# Power.net
KiCad netlist of a schematic drawn in Altium Designer
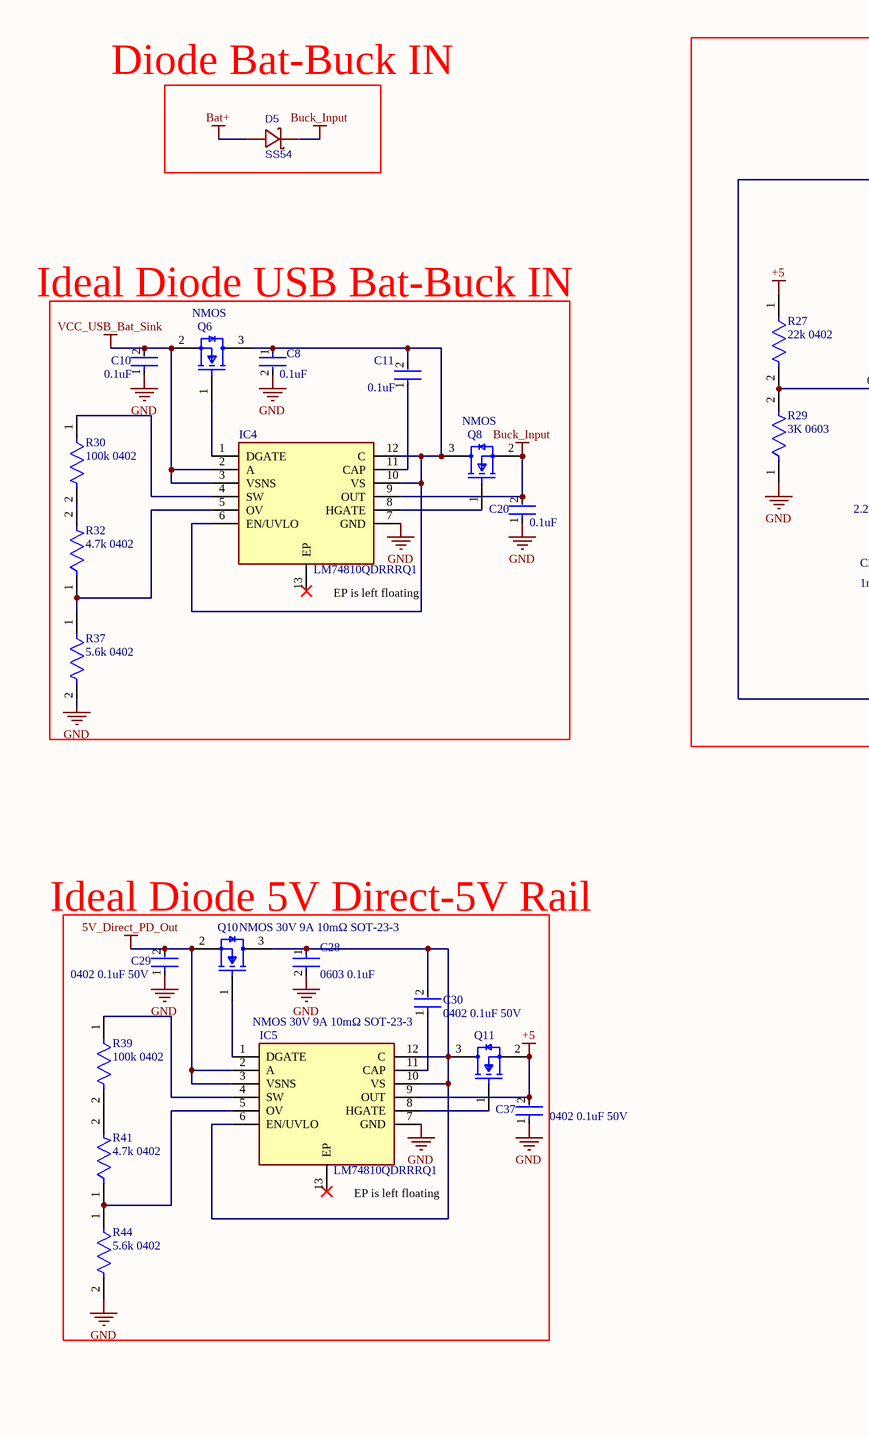
[diagram p0: Power.SchDoc, left]
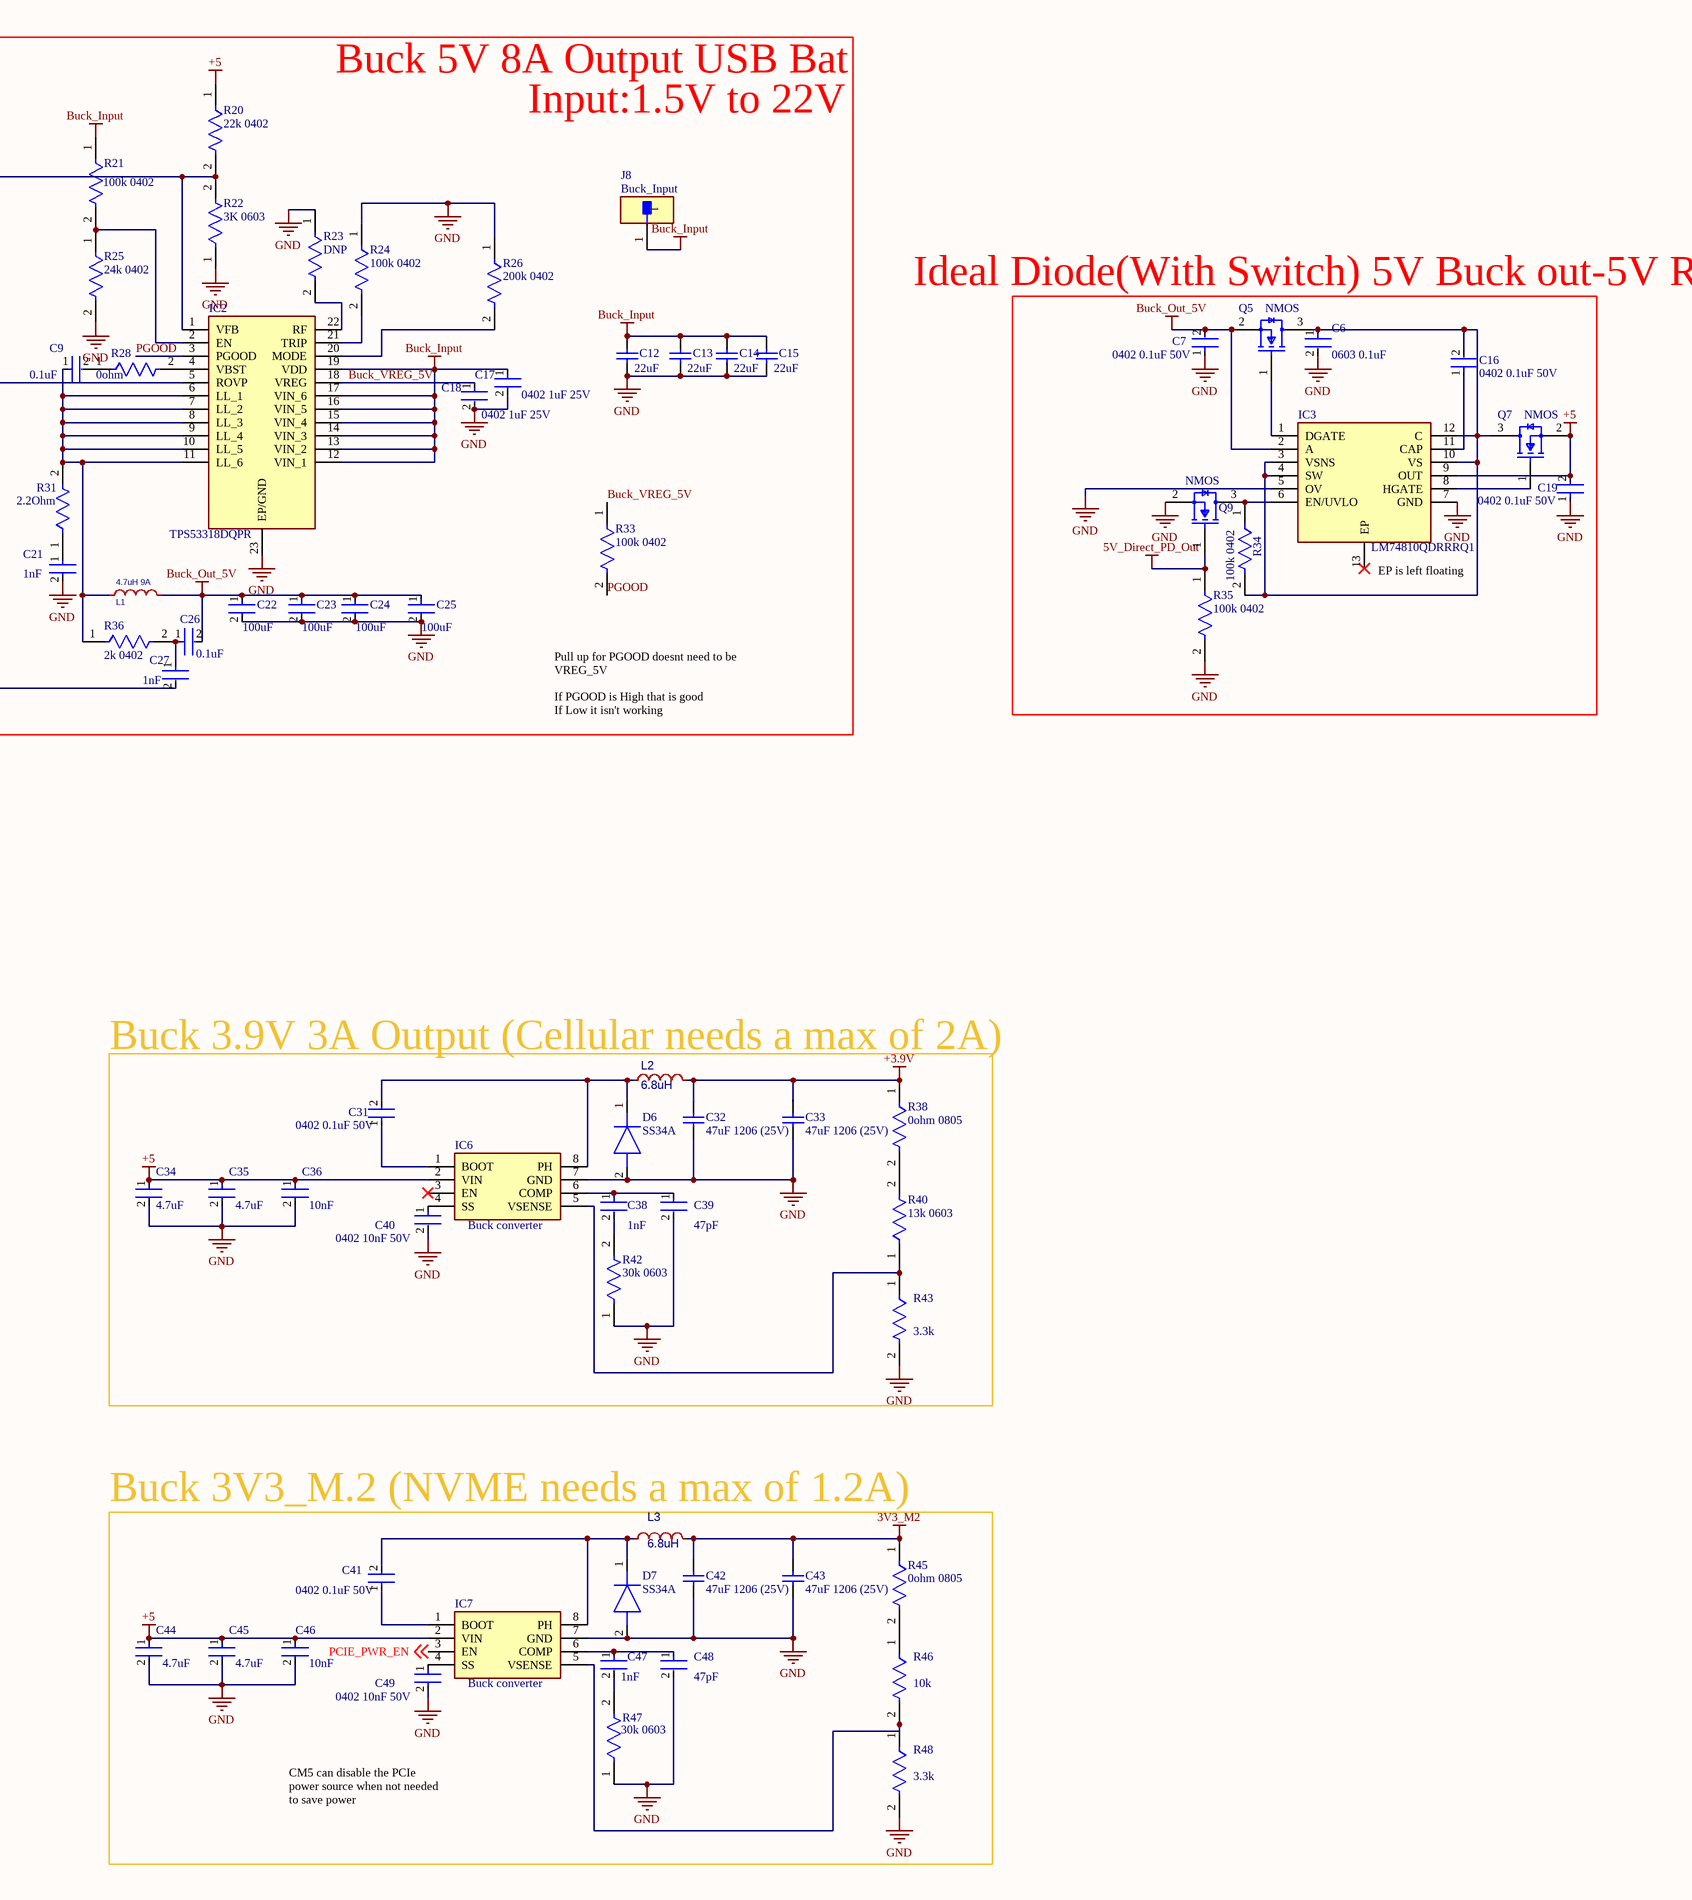
[diagram p1: Power.SchDoc, right]

(export (version "E")
  (design (tool "Eeschema 10.0.6"))
  (components
    (comp (ref "C6")
      (value "0603 0.1uF")
      (footprint "FP-CC0603-DC-MFG")
      (description "C14663")
      (fields (field (name "TOLERANCE") "10%"))
      (libsource (lib "Altium Content Vault") (part "b4654b650e69147ec39a6b967a45e02"))
    )
    (comp (ref "C7")
      (value "0402 0.1uF 50V")
      (footprint "FP-C0402-BB-MFG")
      (description "C307331")
      (fields
        (field (name "TOLERANCE") "0.2")
        (field (name "OCTOPART") "https://octopart.com/c0402c104m3pac7867-kemet-84304880")
      )
      (libsource (lib "Altium Content Vault") (part "b4654b650e69147ec39a6b967a45e02"))
    )
    (comp (ref "C8")
      (value "0.1uF")
      (footprint "FP-CC0603-DC-MFG")
      (description "C14663")
      (fields (field (name "TOLERANCE") "10%"))
      (libsource (lib "Altium Content Vault") (part "b4654b650e69147ec39a6b967a45e02"))
    )
    (comp (ref "C9")
      (value "0.1uF")
      (footprint "FP-C0402-BB-MFG")
      (description "C307331")
      (fields
        (field (name "TOLERANCE") "0.2")
        (field (name "OCTOPART") "https://octopart.com/c0402c104m3pac7867-kemet-84304880")
      )
      (libsource (lib "Altium Content Vault") (part "b4654b650e69147ec39a6b967a45e02"))
    )
    (comp (ref "C10")
      (value "0.1uF")
      (footprint "FP-C0402-BB-MFG")
      (description "C307331")
      (fields
        (field (name "TOLERANCE") "0.2")
        (field (name "OCTOPART") "https://octopart.com/c0402c104m3pac7867-kemet-84304880")
      )
      (libsource (lib "Altium Content Vault") (part "b4654b650e69147ec39a6b967a45e02"))
    )
    (comp (ref "C11")
      (value "0.1uF")
      (footprint "FP-C0402-BB-MFG")
      (description "C307331")
      (fields
        (field (name "TOLERANCE") "0.2")
        (field (name "OCTOPART") "https://octopart.com/c0402c104m3pac7867-kemet-84304880")
      )
      (libsource (lib "Altium Content Vault") (part "b4654b650e69147ec39a6b967a45e02"))
    )
    (comp (ref "C12")
      (value "22uF")
      (footprint "CAPC2013X94X50LL20T25")
      (description "C45783")
      (fields
        (field (name "PART NUMBER") "08051C102KAT4A")
        (field (name "MANUFACTURER") "AVX Interconnect / Elco")
      )
      (libsource (lib "Altium Content Vault") (part "CAP"))
    )
    (comp (ref "C13")
      (value "22uF")
      (footprint "CAPC2013X94X50LL20T25")
      (description "C45783")
      (fields
        (field (name "PART NUMBER") "08051C102KAT4A")
        (field (name "MANUFACTURER") "AVX Interconnect / Elco")
      )
      (libsource (lib "Altium Content Vault") (part "CAP"))
    )
    (comp (ref "C14")
      (value "22uF")
      (footprint "CAPC2013X94X50LL20T25")
      (description "C45783")
      (fields
        (field (name "PART NUMBER") "08051C102KAT4A")
        (field (name "MANUFACTURER") "AVX Interconnect / Elco")
      )
      (libsource (lib "Altium Content Vault") (part "CAP"))
    )
    (comp (ref "C15")
      (value "22uF")
      (footprint "CAPC2013X94X50LL20T25")
      (description "C45783")
      (fields
        (field (name "PART NUMBER") "08051C102KAT4A")
        (field (name "MANUFACTURER") "AVX Interconnect / Elco")
      )
      (libsource (lib "Altium Content Vault") (part "CAP"))
    )
    (comp (ref "C16")
      (value "0402 0.1uF 50V")
      (footprint "FP-C0402-BB-MFG")
      (description "C307331")
      (fields
        (field (name "TOLERANCE") "0.2")
        (field (name "OCTOPART") "https://octopart.com/c0402c104m3pac7867-kemet-84304880")
      )
      (libsource (lib "Altium Content Vault") (part "b4654b650e69147ec39a6b967a45e02"))
    )
    (comp (ref "C17")
      (value "0402 1uF 25V")
      (footprint "FP-C0402-BB-MFG")
      (description "C52923")
      (fields
        (field (name "TOLERANCE") "0.2")
        (field (name "OCTOPART") "https://octopart.com/c0402c104m3pac7867-kemet-84304880")
      )
      (libsource (lib "Altium Content Vault") (part "b4654b650e69147ec39a6b967a45e02"))
    )
    (comp (ref "C18")
      (value "0402 1uF 25V")
      (footprint "FP-C0402-BB-MFG")
      (description "C52923")
      (fields
        (field (name "TOLERANCE") "0.2")
        (field (name "OCTOPART") "https://octopart.com/c0402c104m3pac7867-kemet-84304880")
      )
      (libsource (lib "Altium Content Vault") (part "b4654b650e69147ec39a6b967a45e02"))
    )
    (comp (ref "C19")
      (value "0402 0.1uF 50V")
      (footprint "FP-C0402-BB-MFG")
      (description "C307331")
      (fields
        (field (name "TOLERANCE") "0.2")
        (field (name "OCTOPART") "https://octopart.com/c0402c104m3pac7867-kemet-84304880")
      )
      (libsource (lib "Altium Content Vault") (part "b4654b650e69147ec39a6b967a45e02"))
    )
    (comp (ref "C20")
      (value "0.1uF")
      (footprint "FP-C0402-BB-MFG")
      (description "C307331")
      (fields
        (field (name "TOLERANCE") "0.2")
        (field (name "OCTOPART") "https://octopart.com/c0402c104m3pac7867-kemet-84304880")
      )
      (libsource (lib "Altium Content Vault") (part "b4654b650e69147ec39a6b967a45e02"))
    )
    (comp (ref "C21")
      (value "1nF")
      (footprint "FP-C0402-BB-MFG")
      (description "C1523")
      (fields
        (field (name "TOLERANCE") "0.2")
        (field (name "OCTOPART") "https://octopart.com/c0402c104m3pac7867-kemet-84304880")
      )
      (libsource (lib "Altium Content Vault") (part "b4654b650e69147ec39a6b967a45e02"))
    )
    (comp (ref "C22")
      (value "100uF")
      (footprint "FP-CC1210-GD-IPC_A")
      (description "C7432790")
      (fields (field (name "TOLERANCE") "20%"))
      (libsource (lib "Altium Content Vault") (part "b4654b650e69147ec39a6b967a45e02"))
    )
    (comp (ref "C23")
      (value "100uF")
      (footprint "FP-CC1210-GD-IPC_A")
      (description "C7432790")
      (fields (field (name "TOLERANCE") "20%"))
      (libsource (lib "Altium Content Vault") (part "b4654b650e69147ec39a6b967a45e02"))
    )
    (comp (ref "C24")
      (value "100uF")
      (footprint "FP-CC1210-GD-IPC_A")
      (description "C7432790")
      (fields (field (name "TOLERANCE") "20%"))
      (libsource (lib "Altium Content Vault") (part "b4654b650e69147ec39a6b967a45e02"))
    )
    (comp (ref "C25")
      (value "100uF")
      (footprint "FP-CC1210-GD-IPC_A")
      (description "C7432790")
      (fields (field (name "TOLERANCE") "20%"))
      (libsource (lib "Altium Content Vault") (part "b4654b650e69147ec39a6b967a45e02"))
    )
    (comp (ref "C26")
      (value "0.1uF")
      (footprint "FP-C0402-BB-MFG")
      (description "C307331")
      (fields
        (field (name "TOLERANCE") "0.2")
        (field (name "OCTOPART") "https://octopart.com/c0402c104m3pac7867-kemet-84304880")
      )
      (libsource (lib "Altium Content Vault") (part "b4654b650e69147ec39a6b967a45e02"))
    )
    (comp (ref "C27")
      (value "1nF")
      (footprint "FP-C0402-BB-MFG")
      (description "C1523")
      (fields
        (field (name "TOLERANCE") "0.2")
        (field (name "OCTOPART") "https://octopart.com/c0402c104m3pac7867-kemet-84304880")
      )
      (libsource (lib "Altium Content Vault") (part "b4654b650e69147ec39a6b967a45e02"))
    )
    (comp (ref "C28")
      (value "0603 0.1uF")
      (footprint "FP-CC0603-DC-MFG")
      (description "C14663")
      (fields (field (name "TOLERANCE") "10%"))
      (libsource (lib "Altium Content Vault") (part "b4654b650e69147ec39a6b967a45e02"))
    )
    (comp (ref "C29")
      (value "0402 0.1uF 50V")
      (footprint "FP-C0402-BB-MFG")
      (description "C307331")
      (fields
        (field (name "TOLERANCE") "0.2")
        (field (name "OCTOPART") "https://octopart.com/c0402c104m3pac7867-kemet-84304880")
      )
      (libsource (lib "Altium Content Vault") (part "b4654b650e69147ec39a6b967a45e02"))
    )
    (comp (ref "C30")
      (value "0402 0.1uF 50V")
      (footprint "FP-C0402-BB-MFG")
      (description "C307331")
      (fields
        (field (name "TOLERANCE") "0.2")
        (field (name "OCTOPART") "https://octopart.com/c0402c104m3pac7867-kemet-84304880")
      )
      (libsource (lib "Altium Content Vault") (part "b4654b650e69147ec39a6b967a45e02"))
    )
    (comp (ref "C31")
      (value "0402 0.1uF 50V")
      (footprint "FP-C0402-BB-MFG")
      (description "C307331")
      (fields
        (field (name "TOLERANCE") "0.2")
        (field (name "OCTOPART") "https://octopart.com/c0402c104m3pac7867-kemet-84304880")
      )
      (libsource (lib "Altium Content Vault") (part "b4654b650e69147ec39a6b967a45e02"))
    )
    (comp (ref "C32")
      (value "47uF 1206 (25V)")
      (footprint "CAPC1206(3216)190_N")
      (description "C6119973")
      (fields (field (name "TOLERANCE") "Â±20%"))
      (libsource (lib "Altium Content Vault") (part "CAP"))
    )
    (comp (ref "C33")
      (value "47uF 1206 (25V)")
      (footprint "CAPC1206(3216)190_N")
      (description "C6119973")
      (fields (field (name "TOLERANCE") "Â±20%"))
      (libsource (lib "Altium Content Vault") (part "CAP"))
    )
    (comp (ref "C34")
      (value "4.7uF")
      (footprint "FP-CC0603-DC-MFG")
      (description "C19666")
      (fields (field (name "TOLERANCE") "10%"))
      (libsource (lib "Altium Content Vault") (part "b4654b650e69147ec39a6b967a45e02"))
    )
    (comp (ref "C35")
      (value "4.7uF")
      (footprint "FP-CC0603-DC-MFG")
      (description "C19666")
      (fields (field (name "TOLERANCE") "10%"))
      (libsource (lib "Altium Content Vault") (part "b4654b650e69147ec39a6b967a45e02"))
    )
    (comp (ref "C36")
      (value "10nF")
      (footprint "FP-C0402-BB-MFG")
      (description "C15195")
      (fields
        (field (name "TOLERANCE") "0.2")
        (field (name "OCTOPART") "https://octopart.com/c0402c104m3pac7867-kemet-84304880")
      )
      (libsource (lib "Altium Content Vault") (part "b4654b650e69147ec39a6b967a45e02"))
    )
    (comp (ref "C37")
      (value "0402 0.1uF 50V")
      (footprint "FP-C0402-BB-MFG")
      (description "C307331")
      (fields
        (field (name "TOLERANCE") "0.2")
        (field (name "OCTOPART") "https://octopart.com/c0402c104m3pac7867-kemet-84304880")
      )
      (libsource (lib "Altium Content Vault") (part "b4654b650e69147ec39a6b967a45e02"))
    )
    (comp (ref "C38")
      (value "1nF")
      (footprint "FP-C0402-BB-MFG")
      (description "C1523")
      (fields
        (field (name "TOLERANCE") "0.2")
        (field (name "OCTOPART") "https://octopart.com/c0402c104m3pac7867-kemet-84304880")
      )
      (libsource (lib "Altium Content Vault") (part "b4654b650e69147ec39a6b967a45e02"))
    )
    (comp (ref "C39")
      (value "47pF")
      (footprint "FP-C0402-BB-MFG")
      (description "C1567")
      (fields
        (field (name "TOLERANCE") "0.2")
        (field (name "OCTOPART") "https://octopart.com/c0402c104m3pac7867-kemet-84304880")
      )
      (libsource (lib "Altium Content Vault") (part "b4654b650e69147ec39a6b967a45e02"))
    )
    (comp (ref "C40")
      (value "0402 10nF 50V")
      (footprint "FP-C0402-BB-MFG")
      (description "C15195")
      (fields
        (field (name "TOLERANCE") "0.2")
        (field (name "OCTOPART") "https://octopart.com/c0402c104m3pac7867-kemet-84304880")
      )
      (libsource (lib "Altium Content Vault") (part "b4654b650e69147ec39a6b967a45e02"))
    )
    (comp (ref "C41")
      (value "0402 0.1uF 50V")
      (footprint "FP-C0402-BB-MFG")
      (description "C307331")
      (fields
        (field (name "TOLERANCE") "0.2")
        (field (name "OCTOPART") "https://octopart.com/c0402c104m3pac7867-kemet-84304880")
      )
      (libsource (lib "Altium Content Vault") (part "b4654b650e69147ec39a6b967a45e02"))
    )
    (comp (ref "C42")
      (value "47uF 1206 (25V)")
      (footprint "CAPC1206(3216)190_N")
      (description "C6119973")
      (fields (field (name "TOLERANCE") "Â±20%"))
      (libsource (lib "Altium Content Vault") (part "CAP"))
    )
    (comp (ref "C43")
      (value "47uF 1206 (25V)")
      (footprint "CAPC1206(3216)190_N")
      (description "C6119973")
      (fields (field (name "TOLERANCE") "Â±20%"))
      (libsource (lib "Altium Content Vault") (part "CAP"))
    )
    (comp (ref "C44")
      (value "4.7uF")
      (footprint "FP-CC0603-DC-MFG")
      (description "C19666")
      (fields (field (name "TOLERANCE") "10%"))
      (libsource (lib "Altium Content Vault") (part "b4654b650e69147ec39a6b967a45e02"))
    )
    (comp (ref "C45")
      (value "4.7uF")
      (footprint "FP-CC0603-DC-MFG")
      (description "C19666")
      (fields (field (name "TOLERANCE") "10%"))
      (libsource (lib "Altium Content Vault") (part "b4654b650e69147ec39a6b967a45e02"))
    )
    (comp (ref "C46")
      (value "10nF")
      (footprint "FP-C0402-BB-MFG")
      (description "C15195")
      (fields
        (field (name "TOLERANCE") "0.2")
        (field (name "OCTOPART") "https://octopart.com/c0402c104m3pac7867-kemet-84304880")
      )
      (libsource (lib "Altium Content Vault") (part "b4654b650e69147ec39a6b967a45e02"))
    )
    (comp (ref "C47")
      (value "1nF")
      (footprint "FP-C0402-BB-MFG")
      (description "C1523")
      (fields
        (field (name "TOLERANCE") "0.2")
        (field (name "OCTOPART") "https://octopart.com/c0402c104m3pac7867-kemet-84304880")
      )
      (libsource (lib "Altium Content Vault") (part "b4654b650e69147ec39a6b967a45e02"))
    )
    (comp (ref "C48")
      (value "47pF")
      (footprint "FP-C0402-BB-MFG")
      (description "C1567")
      (fields
        (field (name "TOLERANCE") "0.2")
        (field (name "OCTOPART") "https://octopart.com/c0402c104m3pac7867-kemet-84304880")
      )
      (libsource (lib "Altium Content Vault") (part "b4654b650e69147ec39a6b967a45e02"))
    )
    (comp (ref "C49")
      (value "0402 10nF 50V")
      (footprint "FP-C0402-BB-MFG")
      (description "C15195")
      (fields
        (field (name "TOLERANCE") "0.2")
        (field (name "OCTOPART") "https://octopart.com/c0402c104m3pac7867-kemet-84304880")
      )
      (libsource (lib "Altium Content Vault") (part "b4654b650e69147ec39a6b967a45e02"))
    )
    (comp (ref "D5")
      (value "SS54")
      (footprint "SMB_L4.6-W3.6-LS5.3-RD")
      (description "C32513")
      (fields (field (name "MANUFACTURER PART") "SS54B") (field (name "MANUFACTURER") "MDD(辰达半导体)"))
      (libsource (lib "Schlib1") (part "SS54"))
    )
    (comp (ref "D6")
      (value "SS34A")
      (footprint "SamacSys:DIOM5026X262N")
      (description "C8678")
      (libsource (lib "*") (part "SS34A"))
    )
    (comp (ref "D7")
      (value "SS34A")
      (footprint "SamacSys:DIOM5026X262N")
      (description "C8678")
      (libsource (lib "*") (part "SS34A"))
    )
    (comp (ref "IC2")
      (value "TPS53318DQPR")
      (footprint "PcbLib1:SON50P500X600X150-23N")
      (description "C179745")
      (fields (field (name "MOUSER PART NUMBER") "595-TPS53318DQPR"))
      (libsource (lib "*") (part "TPS53318DQPR"))
    )
    (comp (ref "IC3")
      (value "LM74810QDRRRQ1")
      (footprint "PcbLib1:SON50P300X300X80-13N-D")
      (description "C3215601")
      (fields (field (name "MOUSER PART NUMBER") "595-LM74810QDRRRQ1"))
      (libsource (lib "*") (part "LM74810QDRRRQ1"))
    )
    (comp (ref "IC4")
      (value "LM74810QDRRRQ1")
      (footprint "PcbLib1:SON50P300X300X80-13N-D")
      (description "C3215601")
      (fields (field (name "MOUSER PART NUMBER") "595-LM74810QDRRRQ1"))
      (libsource (lib "*") (part "LM74810QDRRRQ1"))
    )
    (comp (ref "IC5")
      (value "LM74810QDRRRQ1")
      (footprint "PcbLib1:SON50P300X300X80-13N-D")
      (description "C3215601")
      (fields (field (name "MOUSER PART NUMBER") "595-LM74810QDRRRQ1"))
      (libsource (lib "*") (part "LM74810QDRRRQ1"))
    )
    (comp (ref "IC6")
      (value "Buck converter")
      (footprint "SamacSys:SOIC127P600X175-8N")
      (description "C9865")
      (fields
        (field (name "MANUFACTURER_PART_NUMBER") "TPS54331D")
        (field (name "MOUSER PART NUMBER") "595-TPS54331D")
      )
      (libsource (lib "*") (part "TPS54331D"))
    )
    (comp (ref "IC7")
      (value "Buck converter")
      (footprint "SamacSys:SOIC127P600X175-8N")
      (description "C9865")
      (fields
        (field (name "MANUFACTURER_PART_NUMBER") "TPS54331D")
        (field (name "MOUSER PART NUMBER") "595-TPS54331D")
      )
      (libsource (lib "*") (part "TPS54331D"))
    )
    (comp (ref "J8")
      (value "Buck_Input")
      (footprint "FP-5015-MFG")
      (description "PC TEST POINT MINIATURE")
      (fields (field (name "MANUFACTURER PART NUMBER") "5015") (field (name "MANUFACTURER") "keystone"))
      (libsource (lib "Altium Content Vault") (part "dd45045ce8184df9e99e12baf3f412c"))
    )
    (comp (ref "L1")
      (value "4.7uH 9A")
      (footprint "IND-SMD_L11.5-W10.0_FXL1040")
      (description "C5307657")
      (fields (field (name "MANUFACTURER") "XR(祥如)") (field (name "MANUFACTURER PART") "XR1040-4R7M"))
      (libsource (lib "Schlib1") (part "XR1040-4R7M"))
    )
    (comp (ref "L2")
      (value "6.8uH")
      (footprint "IND-SMD_L7.0-W6.6")
      (description "C167221")
      (fields (field (name "MANUFACTURER") "cjiang(长江微电)") (field (name "MANUFACTURER PART") "FXL0630-6R8-M"))
      (libsource (lib "Schlib1") (part "FXL0630-6R8-M"))
    )
    (comp (ref "L3")
      (value "6.8uH")
      (footprint "IND-SMD_L7.0-W6.6")
      (description "C167221")
      (fields (field (name "MANUFACTURER") "cjiang(长江微电)") (field (name "MANUFACTURER PART") "FXL0630-6R8-M"))
      (libsource (lib "Schlib1") (part "FXL0630-6R8-M"))
    )
    (comp (ref "Q5")
      (value "NMOS")
      (footprint "FP-C04-17458-MFG")
      (description "C42374608")
      (libsource (lib "Altium Content Vault") (part "3b9c635fedb024a5347a57b145af9cc"))
    )
    (comp (ref "Q6")
      (value "NMOS")
      (footprint "FP-C04-17458-MFG")
      (description "C42374608")
      (libsource (lib "Altium Content Vault") (part "3b9c635fedb024a5347a57b145af9cc"))
    )
    (comp (ref "Q7")
      (value "NMOS")
      (footprint "FP-C04-17458-MFG")
      (description "C42374608")
      (libsource (lib "Altium Content Vault") (part "3b9c635fedb024a5347a57b145af9cc"))
    )
    (comp (ref "Q8")
      (value "NMOS")
      (footprint "FP-C04-17458-MFG")
      (description "C42374608")
      (libsource (lib "Altium Content Vault") (part "3b9c635fedb024a5347a57b145af9cc"))
    )
    (comp (ref "Q9")
      (value "NMOS")
      (footprint "FP-C04-17458-MFG")
      (description "C42374608")
      (libsource (lib "Altium Content Vault") (part "3b9c635fedb024a5347a57b145af9cc"))
    )
    (comp (ref "Q10")
      (value "NMOS 30V 9A 10mΩ SOT-23-3")
      (footprint "FP-C04-17458-MFG")
      (description "C42374608")
      (libsource (lib "Altium Content Vault") (part "3b9c635fedb024a5347a57b145af9cc"))
    )
    (comp (ref "Q11")
      (value "NMOS 30V 9A 10mΩ SOT-23-3")
      (footprint "FP-C04-17458-MFG")
      (description "C42374608")
      (libsource (lib "Altium Content Vault") (part "3b9c635fedb024a5347a57b145af9cc"))
    )
    (comp (ref "R20")
      (value "22k 0402")
      (footprint "FP-RMCF0402-MFG")
      (description "C25768")
      (fields (field (name "TOLERANCE") "5%"))
      (libsource (lib "Altium Content Vault") (part "1029c3af85768c4190bb7ad29bc67b5"))
    )
    (comp (ref "R21")
      (value "100k 0402")
      (footprint "FP-RMCF0402-MFG")
      (description "C25741")
      (fields (field (name "TOLERANCE") "5%"))
      (libsource (lib "Altium Content Vault") (part "1029c3af85768c4190bb7ad29bc67b5"))
    )
    (comp (ref "R22")
      (value "3K 0603")
      (footprint "FP-RMCF0603-IPC_A")
      (description "C4211")
      (fields (field (name "TOLERANCE") "1%"))
      (libsource (lib "Altium Content Vault") (part "1029c3af85768c4190bb7ad29bc67b5"))
    )
    (comp (ref "R23")
      (value "DNP")
      (footprint "FP-RN73R2A-IPC_C")
      (description "DNP 0805")
      (libsource (lib "Altium Content Vault") (part "1029c3af85768c4190bb7ad29bc67b5"))
    )
    (comp (ref "R24")
      (value "100k 0402")
      (footprint "FP-RMCF0402-MFG")
      (description "C25741")
      (fields (field (name "TOLERANCE") "5%"))
      (libsource (lib "Altium Content Vault") (part "1029c3af85768c4190bb7ad29bc67b5"))
    )
    (comp (ref "R25")
      (value "24k 0402")
      (footprint "FP-RMCF0402-MFG")
      (description "C54530790")
      (fields (field (name "TOLERANCE") "5%"))
      (libsource (lib "Altium Content Vault") (part "1029c3af85768c4190bb7ad29bc67b5"))
    )
    (comp (ref "R26")
      (value "200k 0402")
      (footprint "FP-RMCF0402-MFG")
      (description "C25764")
      (fields (field (name "TOLERANCE") "5%"))
      (libsource (lib "Altium Content Vault") (part "1029c3af85768c4190bb7ad29bc67b5"))
    )
    (comp (ref "R27")
      (value "22k 0402")
      (footprint "FP-RMCF0402-MFG")
      (description "C25768")
      (fields (field (name "TOLERANCE") "5%"))
      (libsource (lib "Altium Content Vault") (part "1029c3af85768c4190bb7ad29bc67b5"))
    )
    (comp (ref "R28")
      (value "0ohm")
      (footprint "FP-RN73R2A-IPC_C")
      (description "C17477")
      (libsource (lib "Altium Content Vault") (part "1029c3af85768c4190bb7ad29bc67b5"))
    )
    (comp (ref "R29")
      (value "3K 0603")
      (footprint "FP-RMCF0603-IPC_A")
      (description "C4211")
      (fields (field (name "TOLERANCE") "1%"))
      (libsource (lib "Altium Content Vault") (part "1029c3af85768c4190bb7ad29bc67b5"))
    )
    (comp (ref "R30")
      (value "100k 0402")
      (footprint "FP-RMCF0402-MFG")
      (description "C25741")
      (fields (field (name "TOLERANCE") "5%"))
      (libsource (lib "Altium Content Vault") (part "1029c3af85768c4190bb7ad29bc67b5"))
    )
    (comp (ref "R31")
      (value "2.2Ohm")
      (footprint "FP-RMCF0603-IPC_A")
      (description "C22939")
      (fields (field (name "TOLERANCE") "1%"))
      (libsource (lib "Altium Content Vault") (part "1029c3af85768c4190bb7ad29bc67b5"))
    )
    (comp (ref "R32")
      (value "4.7k 0402")
      (footprint "FP-RMCF0402-MFG")
      (description "C25900")
      (fields (field (name "TOLERANCE") "5%"))
      (libsource (lib "Altium Content Vault") (part "1029c3af85768c4190bb7ad29bc67b5"))
    )
    (comp (ref "R33")
      (value "100k 0402")
      (footprint "FP-RMCF0402-MFG")
      (description "C25741")
      (fields (field (name "TOLERANCE") "5%"))
      (libsource (lib "Altium Content Vault") (part "1029c3af85768c4190bb7ad29bc67b5"))
    )
    (comp (ref "R34")
      (value "100k 0402")
      (footprint "FP-RMCF0402-MFG")
      (description "C25741")
      (fields (field (name "TOLERANCE") "5%"))
      (libsource (lib "Altium Content Vault") (part "1029c3af85768c4190bb7ad29bc67b5"))
    )
    (comp (ref "R35")
      (value "100k 0402")
      (footprint "FP-RMCF0402-MFG")
      (description "C25741")
      (fields (field (name "TOLERANCE") "5%"))
      (libsource (lib "Altium Content Vault") (part "1029c3af85768c4190bb7ad29bc67b5"))
    )
    (comp (ref "R36")
      (value "2k 0402")
      (footprint "FP-RMCF0402-MFG")
      (description "C4109")
      (fields (field (name "TOLERANCE") "5%"))
      (libsource (lib "Altium Content Vault") (part "1029c3af85768c4190bb7ad29bc67b5"))
    )
    (comp (ref "R37")
      (value "5.6k 0402")
      (footprint "FP-RMCF0402-MFG")
      (description "C25908")
      (fields (field (name "TOLERANCE") "5%"))
      (libsource (lib "Altium Content Vault") (part "1029c3af85768c4190bb7ad29bc67b5"))
    )
    (comp (ref "R38")
      (value "0ohm 0805")
      (footprint "FP-RN73R2A-IPC_C")
      (description "C17477")
      (libsource (lib "Altium Content Vault") (part "1029c3af85768c4190bb7ad29bc67b5"))
    )
    (comp (ref "R39")
      (value "100k 0402")
      (footprint "FP-RMCF0402-MFG")
      (description "C25741")
      (fields (field (name "TOLERANCE") "5%"))
      (libsource (lib "Altium Content Vault") (part "1029c3af85768c4190bb7ad29bc67b5"))
    )
    (comp (ref "R40")
      (value "13k 0603")
      (footprint "FP-RMCF0603-MFG")
      (description "C22797")
      (fields (field (name "TOLERANCE") "1%"))
      (libsource (lib "Altium Content Vault") (part "1029c3af85768c4190bb7ad29bc67b5"))
    )
    (comp (ref "R41")
      (value "4.7k 0402")
      (footprint "FP-RMCF0402-MFG")
      (description "C25900")
      (fields (field (name "TOLERANCE") "5%"))
      (libsource (lib "Altium Content Vault") (part "1029c3af85768c4190bb7ad29bc67b5"))
    )
    (comp (ref "R42")
      (value "30k 0603")
      (footprint "FP-RMCF0603-MFG")
      (description "C22984")
      (fields (field (name "TOLERANCE") "1%"))
      (libsource (lib "Altium Content Vault") (part "1029c3af85768c4190bb7ad29bc67b5"))
    )
    (comp (ref "R43")
      (value "3.3k")
      (footprint "FP-RMCF0402-MFG")
      (description "C25890")
      (fields (field (name "TOLERANCE") "5%"))
      (libsource (lib "Altium Content Vault") (part "1029c3af85768c4190bb7ad29bc67b5"))
    )
    (comp (ref "R44")
      (value "5.6k 0402")
      (footprint "FP-RMCF0402-MFG")
      (description "C25908")
      (fields (field (name "TOLERANCE") "5%"))
      (libsource (lib "Altium Content Vault") (part "1029c3af85768c4190bb7ad29bc67b5"))
    )
    (comp (ref "R45")
      (value "0ohm 0805")
      (footprint "FP-RN73R2A-IPC_C")
      (description "C17477")
      (libsource (lib "Altium Content Vault") (part "1029c3af85768c4190bb7ad29bc67b5"))
    )
    (comp (ref "R46")
      (value "10k")
      (footprint "FP-RMCF0402-MFG")
      (description "C25744")
      (fields (field (name "TOLERANCE") "5%"))
      (libsource (lib "Altium Content Vault") (part "1029c3af85768c4190bb7ad29bc67b5"))
    )
    (comp (ref "R47")
      (value "30k 0603")
      (footprint "FP-RMCF0603-MFG")
      (description "C22984")
      (fields (field (name "TOLERANCE") "1%"))
      (libsource (lib "Altium Content Vault") (part "1029c3af85768c4190bb7ad29bc67b5"))
    )
    (comp (ref "R48")
      (value "3.3k")
      (footprint "FP-RMCF0402-MFG")
      (description "C25890")
      (fields (field (name "TOLERANCE") "5%"))
      (libsource (lib "Altium Content Vault") (part "1029c3af85768c4190bb7ad29bc67b5"))
    )
  )
  (nets
    (net (code "1") (name "+3.9V") (class "Default")
      (node (ref "C32") (pin "2") (pinfunction "2_2") (pintype "passive"))
      (node (ref "C33") (pin "2") (pinfunction "2_2") (pintype "passive"))
      (node (ref "L2") (pin "2") (pinfunction "2_2") (pintype "passive"))
      (node (ref "R38") (pin "1") (pinfunction "1_1") (pintype "passive"))
    )
    (net (code "2") (name "+5") (class "Default")
      (node (ref "C19") (pin "2") (pinfunction "2_2") (pintype "passive"))
      (node (ref "C34") (pin "1") (pinfunction "1_1") (pintype "passive"))
      (node (ref "C35") (pin "1") (pinfunction "1_1") (pintype "passive"))
      (node (ref "C36") (pin "1") (pinfunction "1_1") (pintype "passive"))
      (node (ref "C37") (pin "2") (pinfunction "2_2") (pintype "passive"))
      (node (ref "C44") (pin "1") (pinfunction "1_1") (pintype "passive"))
      (node (ref "C45") (pin "1") (pinfunction "1_1") (pintype "passive"))
      (node (ref "C46") (pin "1") (pinfunction "1_1") (pintype "passive"))
      (node (ref "IC3") (pin "9") (pinfunction "OUT_9") (pintype "passive"))
      (node (ref "IC5") (pin "9") (pinfunction "OUT_9") (pintype "passive"))
      (node (ref "IC6") (pin "2") (pinfunction "VIN_2") (pintype "passive"))
      (node (ref "IC7") (pin "2") (pinfunction "VIN_2") (pintype "passive"))
      (node (ref "Q11") (pin "2") (pinfunction "S_2") (pintype "passive"))
      (node (ref "Q7") (pin "2") (pinfunction "S_2") (pintype "passive"))
      (node (ref "R20") (pin "1") (pinfunction "1_1") (pintype "passive"))
      (node (ref "R27") (pin "1") (pinfunction "1_1") (pintype "passive"))
    )
    (net (code "3") (name "/Buck_VREG_5V") (class "Default")
      (node (ref "C18") (pin "1") (pinfunction "1_1") (pintype "passive"))
      (node (ref "IC2") (pin "18") (pinfunction "VREG_18") (pintype "passive"))
      (node (ref "R33") (pin "1") (pinfunction "1_1") (pintype "passive"))
    )
    (net (code "4") (name "/PGOOD") (class "Default")
      (node (ref "IC2") (pin "3") (pinfunction "PGOOD_3") (pintype "passive"))
      (node (ref "R33") (pin "2") (pinfunction "2_2") (pintype "passive"))
    )
    (net (code "5") (name "3V3_M2") (class "Default")
      (node (ref "C42") (pin "2") (pinfunction "2_2") (pintype "passive"))
      (node (ref "C43") (pin "2") (pinfunction "2_2") (pintype "passive"))
      (node (ref "L3") (pin "2") (pinfunction "2_2") (pintype "passive"))
      (node (ref "R45") (pin "1") (pinfunction "1_1") (pintype "passive"))
    )
    (net (code "6") (name "5V_Direct_PD_Out") (class "Default")
      (node (ref "C29") (pin "2") (pinfunction "2_2") (pintype "passive"))
      (node (ref "IC5") (pin "2") (pinfunction "A_2") (pintype "passive"))
      (node (ref "IC5") (pin "3") (pinfunction "VSNS_3") (pintype "passive"))
      (node (ref "Q10") (pin "2") (pinfunction "S_2") (pintype "passive"))
      (node (ref "Q9") (pin "1") (pinfunction "G_1") (pintype "passive"))
      (node (ref "R35") (pin "1") (pinfunction "1_1") (pintype "passive"))
    )
    (net (code "7") (name "Bat+") (class "Default")
      (node (ref "D5") (pin "2") (pinfunction "A_2") (pintype "passive"))
    )
    (net (code "8") (name "Buck_Input") (class "Default")
      (node (ref "C12") (pin "1") (pinfunction "1_1") (pintype "passive"))
      (node (ref "C13") (pin "1") (pinfunction "1_1") (pintype "passive"))
      (node (ref "C14") (pin "1") (pinfunction "1_1") (pintype "passive"))
      (node (ref "C15") (pin "1") (pinfunction "1_1") (pintype "passive"))
      (node (ref "C17") (pin "1") (pinfunction "1_1") (pintype "passive"))
      (node (ref "C20") (pin "2") (pinfunction "2_2") (pintype "passive"))
      (node (ref "D5") (pin "1") (pinfunction "K_1") (pintype "passive"))
      (node (ref "IC2") (pin "12") (pinfunction "VIN_1_12") (pintype "passive"))
      (node (ref "IC2") (pin "13") (pinfunction "VIN_2_13") (pintype "passive"))
      (node (ref "IC2") (pin "14") (pinfunction "VIN_3_14") (pintype "passive"))
      (node (ref "IC2") (pin "15") (pinfunction "VIN_4_15") (pintype "passive"))
      (node (ref "IC2") (pin "16") (pinfunction "VIN_5_16") (pintype "passive"))
      (node (ref "IC2") (pin "17") (pinfunction "VIN_6_17") (pintype "passive"))
      (node (ref "IC2") (pin "19") (pinfunction "VDD_19") (pintype "passive"))
      (node (ref "IC4") (pin "9") (pinfunction "OUT_9") (pintype "passive"))
      (node (ref "J8") (pin "1") (pinfunction "1_1") (pintype "passive"))
      (node (ref "Q8") (pin "2") (pinfunction "S_2") (pintype "passive"))
      (node (ref "R21") (pin "1") (pinfunction "1_1") (pintype "passive"))
    )
    (net (code "9") (name "Buck_Out_5V") (class "Default")
      (node (ref "C22") (pin "1") (pinfunction "1_1") (pintype "passive"))
      (node (ref "C23") (pin "1") (pinfunction "1_1") (pintype "passive"))
      (node (ref "C24") (pin "1") (pinfunction "1_1") (pintype "passive"))
      (node (ref "C25") (pin "1") (pinfunction "1_1") (pintype "passive"))
      (node (ref "C26") (pin "2") (pinfunction "2_2") (pintype "passive"))
      (node (ref "C7") (pin "2") (pinfunction "2_2") (pintype "passive"))
      (node (ref "IC3") (pin "2") (pinfunction "A_2") (pintype "passive"))
      (node (ref "L1") (pin "2") (pinfunction "2_2") (pintype "passive"))
      (node (ref "Q5") (pin "2") (pinfunction "S_2") (pintype "passive"))
    )
    (net (code "10") (name "GND") (class "Default")
      (node (ref "C10") (pin "1") (pinfunction "1_1") (pintype "passive"))
      (node (ref "C12") (pin "2") (pinfunction "2_2") (pintype "passive"))
      (node (ref "C13") (pin "2") (pinfunction "2_2") (pintype "passive"))
      (node (ref "C14") (pin "2") (pinfunction "2_2") (pintype "passive"))
      (node (ref "C15") (pin "2") (pinfunction "2_2") (pintype "passive"))
      (node (ref "C17") (pin "2") (pinfunction "2_2") (pintype "passive"))
      (node (ref "C18") (pin "2") (pinfunction "2_2") (pintype "passive"))
      (node (ref "C19") (pin "1") (pinfunction "1_1") (pintype "passive"))
      (node (ref "C20") (pin "1") (pinfunction "1_1") (pintype "passive"))
      (node (ref "C21") (pin "2") (pinfunction "2_2") (pintype "passive"))
      (node (ref "C22") (pin "2") (pinfunction "2_2") (pintype "passive"))
      (node (ref "C23") (pin "2") (pinfunction "2_2") (pintype "passive"))
      (node (ref "C24") (pin "2") (pinfunction "2_2") (pintype "passive"))
      (node (ref "C25") (pin "2") (pinfunction "2_2") (pintype "passive"))
      (node (ref "C28") (pin "2") (pinfunction "2_2") (pintype "passive"))
      (node (ref "C29") (pin "1") (pinfunction "1_1") (pintype "passive"))
      (node (ref "C32") (pin "1") (pinfunction "1_1") (pintype "passive"))
      (node (ref "C33") (pin "1") (pinfunction "1_1") (pintype "passive"))
      (node (ref "C34") (pin "2") (pinfunction "2_2") (pintype "passive"))
      (node (ref "C35") (pin "2") (pinfunction "2_2") (pintype "passive"))
      (node (ref "C36") (pin "2") (pinfunction "2_2") (pintype "passive"))
      (node (ref "C37") (pin "1") (pinfunction "1_1") (pintype "passive"))
      (node (ref "C39") (pin "2") (pinfunction "2_2") (pintype "passive"))
      (node (ref "C40") (pin "2") (pinfunction "2_2") (pintype "passive"))
      (node (ref "C42") (pin "1") (pinfunction "1_1") (pintype "passive"))
      (node (ref "C43") (pin "1") (pinfunction "1_1") (pintype "passive"))
      (node (ref "C44") (pin "2") (pinfunction "2_2") (pintype "passive"))
      (node (ref "C45") (pin "2") (pinfunction "2_2") (pintype "passive"))
      (node (ref "C46") (pin "2") (pinfunction "2_2") (pintype "passive"))
      (node (ref "C48") (pin "2") (pinfunction "2_2") (pintype "passive"))
      (node (ref "C49") (pin "2") (pinfunction "2_2") (pintype "passive"))
      (node (ref "C6") (pin "2") (pinfunction "2_2") (pintype "passive"))
      (node (ref "C7") (pin "1") (pinfunction "1_1") (pintype "passive"))
      (node (ref "C8") (pin "2") (pinfunction "2_2") (pintype "passive"))
      (node (ref "D6") (pin "2") (pinfunction "A_2") (pintype "passive"))
      (node (ref "D7") (pin "2") (pinfunction "A_2") (pintype "passive"))
      (node (ref "IC2") (pin "23") (pinfunction "EP/GND_23") (pintype "passive"))
      (node (ref "IC3") (pin "5") (pinfunction "OV_5") (pintype "passive"))
      (node (ref "IC3") (pin "7") (pinfunction "GND_7") (pintype "passive"))
      (node (ref "IC4") (pin "7") (pinfunction "GND_7") (pintype "passive"))
      (node (ref "IC5") (pin "7") (pinfunction "GND_7") (pintype "passive"))
      (node (ref "IC6") (pin "7") (pinfunction "GND_7") (pintype "passive"))
      (node (ref "IC7") (pin "7") (pinfunction "GND_7") (pintype "passive"))
      (node (ref "Q9") (pin "2") (pinfunction "S_2") (pintype "passive"))
      (node (ref "R22") (pin "1") (pinfunction "1_1") (pintype "passive"))
      (node (ref "R23") (pin "1") (pinfunction "1_1") (pintype "passive"))
      (node (ref "R24") (pin "1") (pinfunction "1_1") (pintype "passive"))
      (node (ref "R25") (pin "2") (pinfunction "2_2") (pintype "passive"))
      (node (ref "R26") (pin "1") (pinfunction "1_1") (pintype "passive"))
      (node (ref "R29") (pin "1") (pinfunction "1_1") (pintype "passive"))
      (node (ref "R35") (pin "2") (pinfunction "2_2") (pintype "passive"))
      (node (ref "R37") (pin "2") (pinfunction "2_2") (pintype "passive"))
      (node (ref "R42") (pin "1") (pinfunction "1_1") (pintype "passive"))
      (node (ref "R43") (pin "2") (pinfunction "2_2") (pintype "passive"))
      (node (ref "R44") (pin "2") (pinfunction "2_2") (pintype "passive"))
      (node (ref "R47") (pin "1") (pinfunction "1_1") (pintype "passive"))
      (node (ref "R48") (pin "2") (pinfunction "2_2") (pintype "passive"))
    )
    (net (code "11") (name "Net-(C9-Pad2)") (class "Default")
      (node (ref "C9") (pin "2") (pinfunction "2_2") (pintype "passive"))
      (node (ref "R28") (pin "1") (pinfunction "1_1") (pintype "passive"))
    )
    (net (code "12") (name "Net-(C21-Pad1)") (class "Default")
      (node (ref "C21") (pin "1") (pinfunction "1_1") (pintype "passive"))
      (node (ref "R31") (pin "1") (pinfunction "1_1") (pintype "passive"))
    )
    (net (code "13") (name "Net-(C26-Pad1)") (class "Default")
      (node (ref "C26") (pin "1") (pinfunction "1_1") (pintype "passive"))
      (node (ref "C27") (pin "1") (pinfunction "1_1") (pintype "passive"))
      (node (ref "R36") (pin "2") (pinfunction "2_2") (pintype "passive"))
    )
    (net (code "14") (name "Net-(C38-Pad2)") (class "Default")
      (node (ref "C38") (pin "2") (pinfunction "2_2") (pintype "passive"))
      (node (ref "R42") (pin "2") (pinfunction "2_2") (pintype "passive"))
    )
    (net (code "15") (name "Net-(C47-Pad2)") (class "Default")
      (node (ref "C47") (pin "2") (pinfunction "2_2") (pintype "passive"))
      (node (ref "R47") (pin "2") (pinfunction "2_2") (pintype "passive"))
    )
    (net (code "16") (name "Net-(D6-K)") (class "Default")
      (node (ref "C31") (pin "2") (pinfunction "2_2") (pintype "passive"))
      (node (ref "D6") (pin "1") (pinfunction "K_1") (pintype "passive"))
      (node (ref "IC6") (pin "8") (pinfunction "PH_8") (pintype "passive"))
      (node (ref "L2") (pin "1") (pinfunction "1_1") (pintype "passive"))
    )
    (net (code "17") (name "Net-(D7-K)") (class "Default")
      (node (ref "C41") (pin "2") (pinfunction "2_2") (pintype "passive"))
      (node (ref "D7") (pin "1") (pinfunction "K_1") (pintype "passive"))
      (node (ref "IC7") (pin "8") (pinfunction "PH_8") (pintype "passive"))
      (node (ref "L3") (pin "1") (pinfunction "1_1") (pintype "passive"))
    )
    (net (code "18") (name "Net-(IC2-EN)") (class "Default")
      (node (ref "IC2") (pin "2") (pinfunction "EN_2") (pintype "passive"))
      (node (ref "R21") (pin "2") (pinfunction "2_2") (pintype "passive"))
      (node (ref "R25") (pin "1") (pinfunction "1_1") (pintype "passive"))
    )
    (net (code "19") (name "Net-(IC2-LL_1)") (class "Default")
      (node (ref "C9") (pin "1") (pinfunction "1_1") (pintype "passive"))
      (node (ref "IC2") (pin "10") (pinfunction "LL_5_10") (pintype "passive"))
      (node (ref "IC2") (pin "11") (pinfunction "LL_6_11") (pintype "passive"))
      (node (ref "IC2") (pin "6") (pinfunction "LL_1_6") (pintype "passive"))
      (node (ref "IC2") (pin "7") (pinfunction "LL_2_7") (pintype "passive"))
      (node (ref "IC2") (pin "8") (pinfunction "LL_3_8") (pintype "passive"))
      (node (ref "IC2") (pin "9") (pinfunction "LL_4_9") (pintype "passive"))
      (node (ref "L1") (pin "1") (pinfunction "1_1") (pintype "passive"))
      (node (ref "R31") (pin "2") (pinfunction "2_2") (pintype "passive"))
      (node (ref "R36") (pin "1") (pinfunction "1_1") (pintype "passive"))
    )
    (net (code "20") (name "Net-(IC2-MODE)") (class "Default")
      (node (ref "IC2") (pin "20") (pinfunction "MODE_20") (pintype "passive"))
      (node (ref "R26") (pin "2") (pinfunction "2_2") (pintype "passive"))
    )
    (net (code "21") (name "Net-(IC2-RF)") (class "Default")
      (node (ref "IC2") (pin "22") (pinfunction "RF_22") (pintype "passive"))
      (node (ref "R23") (pin "2") (pinfunction "2_2") (pintype "passive"))
    )
    (net (code "22") (name "Net-(IC2-ROVP)") (class "Default")
      (node (ref "IC2") (pin "5") (pinfunction "ROVP_5") (pintype "passive"))
      (node (ref "R27") (pin "2") (pinfunction "2_2") (pintype "passive"))
      (node (ref "R29") (pin "2") (pinfunction "2_2") (pintype "passive"))
    )
    (net (code "23") (name "Net-(IC2-TRIP)") (class "Default")
      (node (ref "IC2") (pin "21") (pinfunction "TRIP_21") (pintype "passive"))
      (node (ref "R24") (pin "2") (pinfunction "2_2") (pintype "passive"))
    )
    (net (code "24") (name "Net-(IC2-VBST)") (class "Default")
      (node (ref "IC2") (pin "4") (pinfunction "VBST_4") (pintype "passive"))
      (node (ref "R28") (pin "2") (pinfunction "2_2") (pintype "passive"))
    )
    (net (code "25") (name "Net-(IC2-VFB)") (class "Default")
      (node (ref "C27") (pin "2") (pinfunction "2_2") (pintype "passive"))
      (node (ref "IC2") (pin "1") (pinfunction "VFB_1") (pintype "passive"))
      (node (ref "R20") (pin "2") (pinfunction "2_2") (pintype "passive"))
      (node (ref "R22") (pin "2") (pinfunction "2_2") (pintype "passive"))
    )
    (net (code "26") (name "Net-(IC3-C)") (class "Default")
      (node (ref "C16") (pin "2") (pinfunction "2_2") (pintype "passive"))
      (node (ref "C6") (pin "1") (pinfunction "1_1") (pintype "passive"))
      (node (ref "IC3") (pin "10") (pinfunction "VS_10") (pintype "passive"))
      (node (ref "IC3") (pin "12") (pinfunction "C_12") (pintype "passive"))
      (node (ref "IC3") (pin "3") (pinfunction "VSNS_3") (pintype "passive"))
      (node (ref "IC3") (pin "4") (pinfunction "SW_4") (pintype "passive"))
      (node (ref "Q5") (pin "3") (pinfunction "D_3") (pintype "passive"))
      (node (ref "Q7") (pin "3") (pinfunction "D_3") (pintype "passive"))
      (node (ref "R34") (pin "2") (pinfunction "2_2") (pintype "passive"))
    )
    (net (code "27") (name "Net-(IC3-CAP)") (class "Default")
      (node (ref "C16") (pin "1") (pinfunction "1_1") (pintype "passive"))
      (node (ref "IC3") (pin "11") (pinfunction "CAP_11") (pintype "passive"))
    )
    (net (code "28") (name "Net-(IC3-DGATE)") (class "Default")
      (node (ref "IC3") (pin "1") (pinfunction "DGATE_1") (pintype "passive"))
      (node (ref "Q5") (pin "1") (pinfunction "G_1") (pintype "passive"))
    )
    (net (code "29") (name "Net-(IC3-EN{slash}UVLO)") (class "Default")
      (node (ref "IC3") (pin "6") (pinfunction "EN/UVLO_6") (pintype "passive"))
      (node (ref "Q9") (pin "3") (pinfunction "D_3") (pintype "passive"))
      (node (ref "R34") (pin "1") (pinfunction "1_1") (pintype "passive"))
    )
    (net (code "30") (name "Net-(IC3-HGATE)") (class "Default")
      (node (ref "IC3") (pin "8") (pinfunction "HGATE_8") (pintype "passive"))
      (node (ref "Q7") (pin "1") (pinfunction "G_1") (pintype "passive"))
    )
    (net (code "31") (name "Net-(IC4-C)") (class "Default")
      (node (ref "C11") (pin "2") (pinfunction "2_2") (pintype "passive"))
      (node (ref "C8") (pin "1") (pinfunction "1_1") (pintype "passive"))
      (node (ref "IC4") (pin "10") (pinfunction "VS_10") (pintype "passive"))
      (node (ref "IC4") (pin "12") (pinfunction "C_12") (pintype "passive"))
      (node (ref "IC4") (pin "6") (pinfunction "EN/UVLO_6") (pintype "passive"))
      (node (ref "Q6") (pin "3") (pinfunction "D_3") (pintype "passive"))
      (node (ref "Q8") (pin "3") (pinfunction "D_3") (pintype "passive"))
    )
    (net (code "32") (name "Net-(IC4-CAP)") (class "Default")
      (node (ref "C11") (pin "1") (pinfunction "1_1") (pintype "passive"))
      (node (ref "IC4") (pin "11") (pinfunction "CAP_11") (pintype "passive"))
    )
    (net (code "33") (name "Net-(IC4-DGATE)") (class "Default")
      (node (ref "IC4") (pin "1") (pinfunction "DGATE_1") (pintype "passive"))
      (node (ref "Q6") (pin "1") (pinfunction "G_1") (pintype "passive"))
    )
    (net (code "34") (name "Net-(IC4-HGATE)") (class "Default")
      (node (ref "IC4") (pin "8") (pinfunction "HGATE_8") (pintype "passive"))
      (node (ref "Q8") (pin "1") (pinfunction "G_1") (pintype "passive"))
    )
    (net (code "35") (name "Net-(IC4-OV)") (class "Default")
      (node (ref "IC4") (pin "5") (pinfunction "OV_5") (pintype "passive"))
      (node (ref "R32") (pin "1") (pinfunction "1_1") (pintype "passive"))
      (node (ref "R37") (pin "1") (pinfunction "1_1") (pintype "passive"))
    )
    (net (code "36") (name "Net-(IC4-SW)") (class "Default")
      (node (ref "IC4") (pin "4") (pinfunction "SW_4") (pintype "passive"))
      (node (ref "R30") (pin "1") (pinfunction "1_1") (pintype "passive"))
    )
    (net (code "37") (name "Net-(IC5-C)") (class "Default")
      (node (ref "C28") (pin "1") (pinfunction "1_1") (pintype "passive"))
      (node (ref "C30") (pin "2") (pinfunction "2_2") (pintype "passive"))
      (node (ref "IC5") (pin "10") (pinfunction "VS_10") (pintype "passive"))
      (node (ref "IC5") (pin "12") (pinfunction "C_12") (pintype "passive"))
      (node (ref "IC5") (pin "6") (pinfunction "EN/UVLO_6") (pintype "passive"))
      (node (ref "Q10") (pin "3") (pinfunction "D_3") (pintype "passive"))
      (node (ref "Q11") (pin "3") (pinfunction "D_3") (pintype "passive"))
    )
    (net (code "38") (name "Net-(IC5-CAP)") (class "Default")
      (node (ref "C30") (pin "1") (pinfunction "1_1") (pintype "passive"))
      (node (ref "IC5") (pin "11") (pinfunction "CAP_11") (pintype "passive"))
    )
    (net (code "39") (name "Net-(IC5-DGATE)") (class "Default")
      (node (ref "IC5") (pin "1") (pinfunction "DGATE_1") (pintype "passive"))
      (node (ref "Q10") (pin "1") (pinfunction "G_1") (pintype "passive"))
    )
    (net (code "40") (name "Net-(IC5-HGATE)") (class "Default")
      (node (ref "IC5") (pin "8") (pinfunction "HGATE_8") (pintype "passive"))
      (node (ref "Q11") (pin "1") (pinfunction "G_1") (pintype "passive"))
    )
    (net (code "41") (name "Net-(IC5-OV)") (class "Default")
      (node (ref "IC5") (pin "5") (pinfunction "OV_5") (pintype "passive"))
      (node (ref "R41") (pin "1") (pinfunction "1_1") (pintype "passive"))
      (node (ref "R44") (pin "1") (pinfunction "1_1") (pintype "passive"))
    )
    (net (code "42") (name "Net-(IC5-SW)") (class "Default")
      (node (ref "IC5") (pin "4") (pinfunction "SW_4") (pintype "passive"))
      (node (ref "R39") (pin "1") (pinfunction "1_1") (pintype "passive"))
    )
    (net (code "43") (name "Net-(IC6-BOOT)") (class "Default")
      (node (ref "C31") (pin "1") (pinfunction "1_1") (pintype "passive"))
      (node (ref "IC6") (pin "1") (pinfunction "BOOT_1") (pintype "passive"))
    )
    (net (code "44") (name "Net-(IC6-COMP)") (class "Default")
      (node (ref "C38") (pin "1") (pinfunction "1_1") (pintype "passive"))
      (node (ref "C39") (pin "1") (pinfunction "1_1") (pintype "passive"))
      (node (ref "IC6") (pin "6") (pinfunction "COMP_6") (pintype "passive"))
    )
    (net (code "45") (name "Net-(IC6-SS)") (class "Default")
      (node (ref "C40") (pin "1") (pinfunction "1_1") (pintype "passive"))
      (node (ref "IC6") (pin "4") (pinfunction "SS_4") (pintype "passive"))
    )
    (net (code "46") (name "Net-(IC6-VSENSE)") (class "Default")
      (node (ref "IC6") (pin "5") (pinfunction "VSENSE_5") (pintype "passive"))
      (node (ref "R40") (pin "1") (pinfunction "1_1") (pintype "passive"))
      (node (ref "R43") (pin "1") (pinfunction "1_1") (pintype "passive"))
    )
    (net (code "47") (name "Net-(IC7-BOOT)") (class "Default")
      (node (ref "C41") (pin "1") (pinfunction "1_1") (pintype "passive"))
      (node (ref "IC7") (pin "1") (pinfunction "BOOT_1") (pintype "passive"))
    )
    (net (code "48") (name "Net-(IC7-COMP)") (class "Default")
      (node (ref "C47") (pin "1") (pinfunction "1_1") (pintype "passive"))
      (node (ref "C48") (pin "1") (pinfunction "1_1") (pintype "passive"))
      (node (ref "IC7") (pin "6") (pinfunction "COMP_6") (pintype "passive"))
    )
    (net (code "49") (name "Net-(IC7-SS)") (class "Default")
      (node (ref "C49") (pin "1") (pinfunction "1_1") (pintype "passive"))
      (node (ref "IC7") (pin "4") (pinfunction "SS_4") (pintype "passive"))
    )
    (net (code "50") (name "Net-(IC7-VSENSE)") (class "Default")
      (node (ref "IC7") (pin "5") (pinfunction "VSENSE_5") (pintype "passive"))
      (node (ref "R46") (pin "2") (pinfunction "2_2") (pintype "passive"))
      (node (ref "R48") (pin "1") (pinfunction "1_1") (pintype "passive"))
    )
    (net (code "51") (name "Net-(R30-Pad2)") (class "Default")
      (node (ref "R30") (pin "2") (pinfunction "2_2") (pintype "passive"))
      (node (ref "R32") (pin "2") (pinfunction "2_2") (pintype "passive"))
    )
    (net (code "52") (name "Net-(R38-Pad2)") (class "Default")
      (node (ref "R38") (pin "2") (pinfunction "2_2") (pintype "passive"))
      (node (ref "R40") (pin "2") (pinfunction "2_2") (pintype "passive"))
    )
    (net (code "53") (name "Net-(R39-Pad2)") (class "Default")
      (node (ref "R39") (pin "2") (pinfunction "2_2") (pintype "passive"))
      (node (ref "R41") (pin "2") (pinfunction "2_2") (pintype "passive"))
    )
    (net (code "54") (name "Net-(R45-Pad2)") (class "Default")
      (node (ref "R45") (pin "2") (pinfunction "2_2") (pintype "passive"))
      (node (ref "R46") (pin "1") (pinfunction "1_1") (pintype "passive"))
    )
    (net (code "55") (name "PCIE_PWR_EN") (class "Default")
      (node (ref "IC7") (pin "3") (pinfunction "EN_3") (pintype "passive"))
    )
    (net (code "56") (name "VCC_USB_Bat_Sink") (class "Default")
      (node (ref "C10") (pin "2") (pinfunction "2_2") (pintype "passive"))
      (node (ref "IC4") (pin "2") (pinfunction "A_2") (pintype "passive"))
      (node (ref "IC4") (pin "3") (pinfunction "VSNS_3") (pintype "passive"))
      (node (ref "Q6") (pin "2") (pinfunction "S_2") (pintype "passive"))
    )
    (net (code "57") (name "unconnected-(IC3-EP-Pad13)") (class "Default")
      (node (ref "IC3") (pin "13") (pinfunction "EP_13") (pintype "passive+no_connect"))
    )
    (net (code "58") (name "unconnected-(IC4-EP-Pad13)") (class "Default")
      (node (ref "IC4") (pin "13") (pinfunction "EP_13") (pintype "passive+no_connect"))
    )
    (net (code "59") (name "unconnected-(IC5-EP-Pad13)") (class "Default")
      (node (ref "IC5") (pin "13") (pinfunction "EP_13") (pintype "passive+no_connect"))
    )
    (net (code "60") (name "unconnected-(IC6-EN-Pad3)") (class "Default")
      (node (ref "IC6") (pin "3") (pinfunction "EN_3") (pintype "passive+no_connect"))
    )
  )
)
